# PCB.net
KiCad netlist of a schematic drawn in Altium Designer
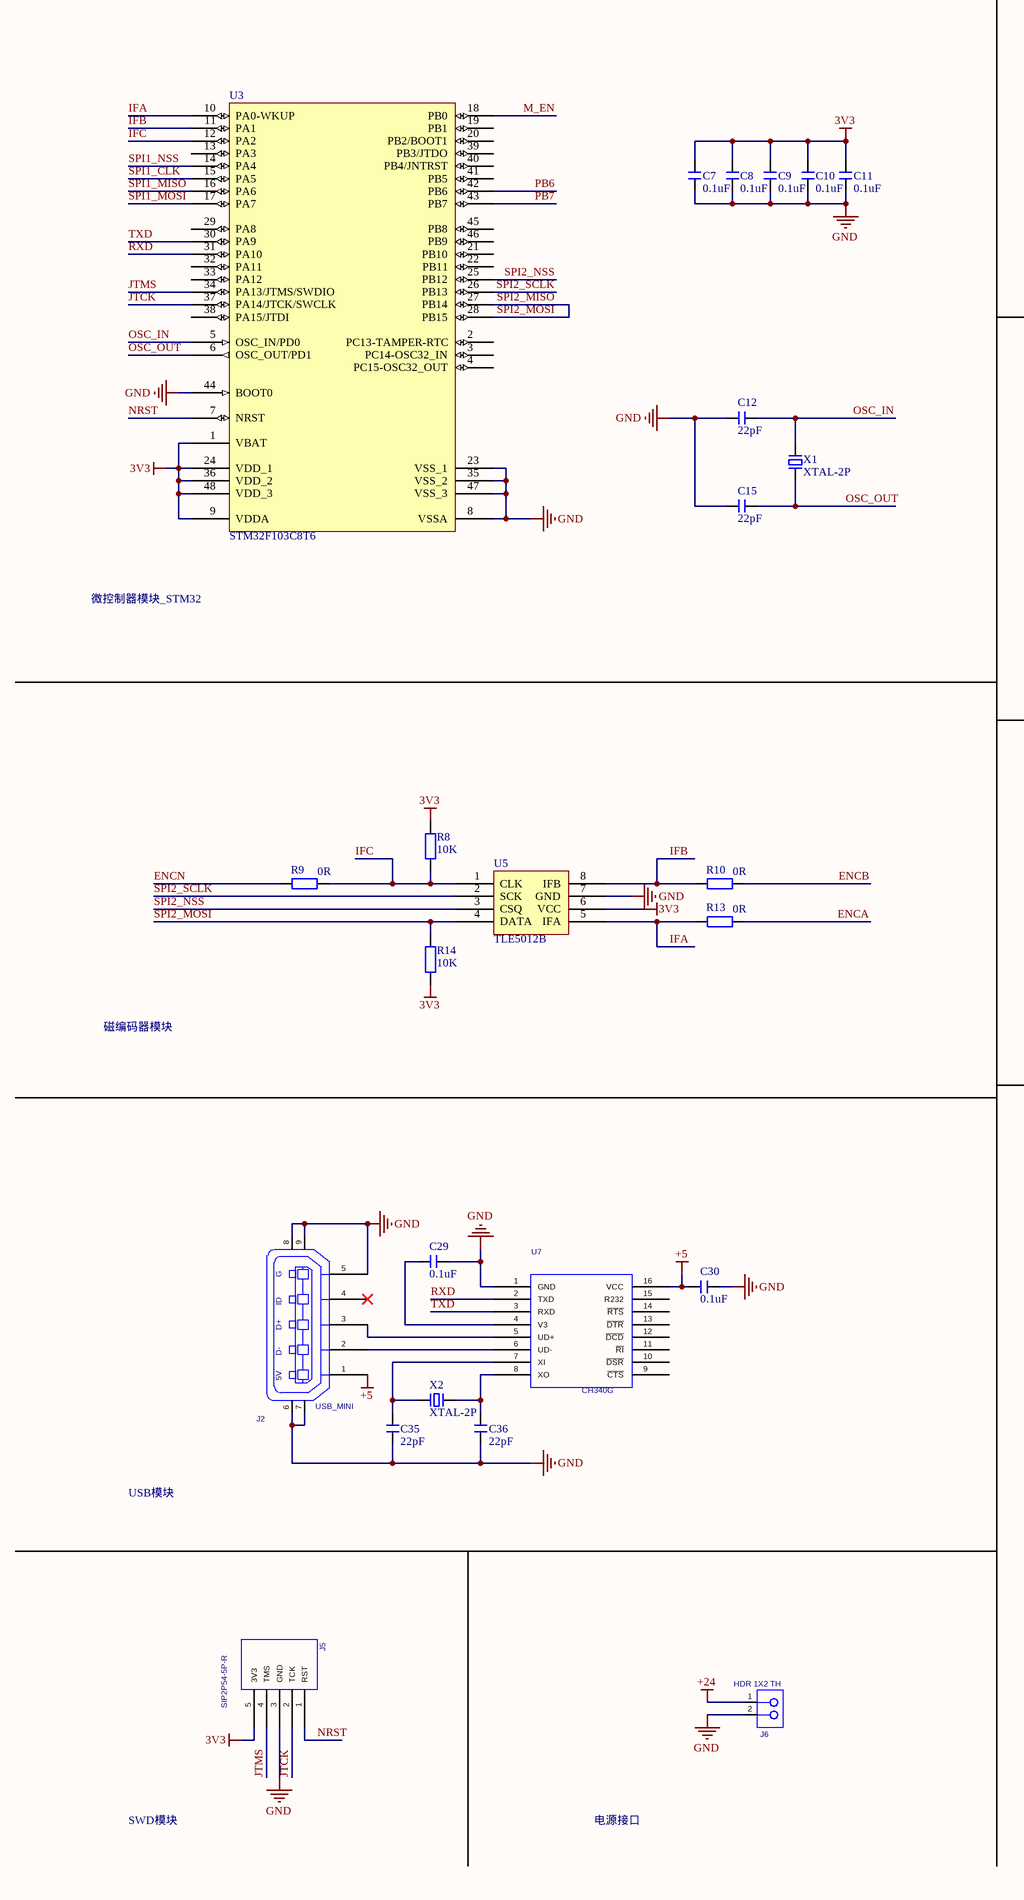
[diagram p0: PCB.SchDoc, left]
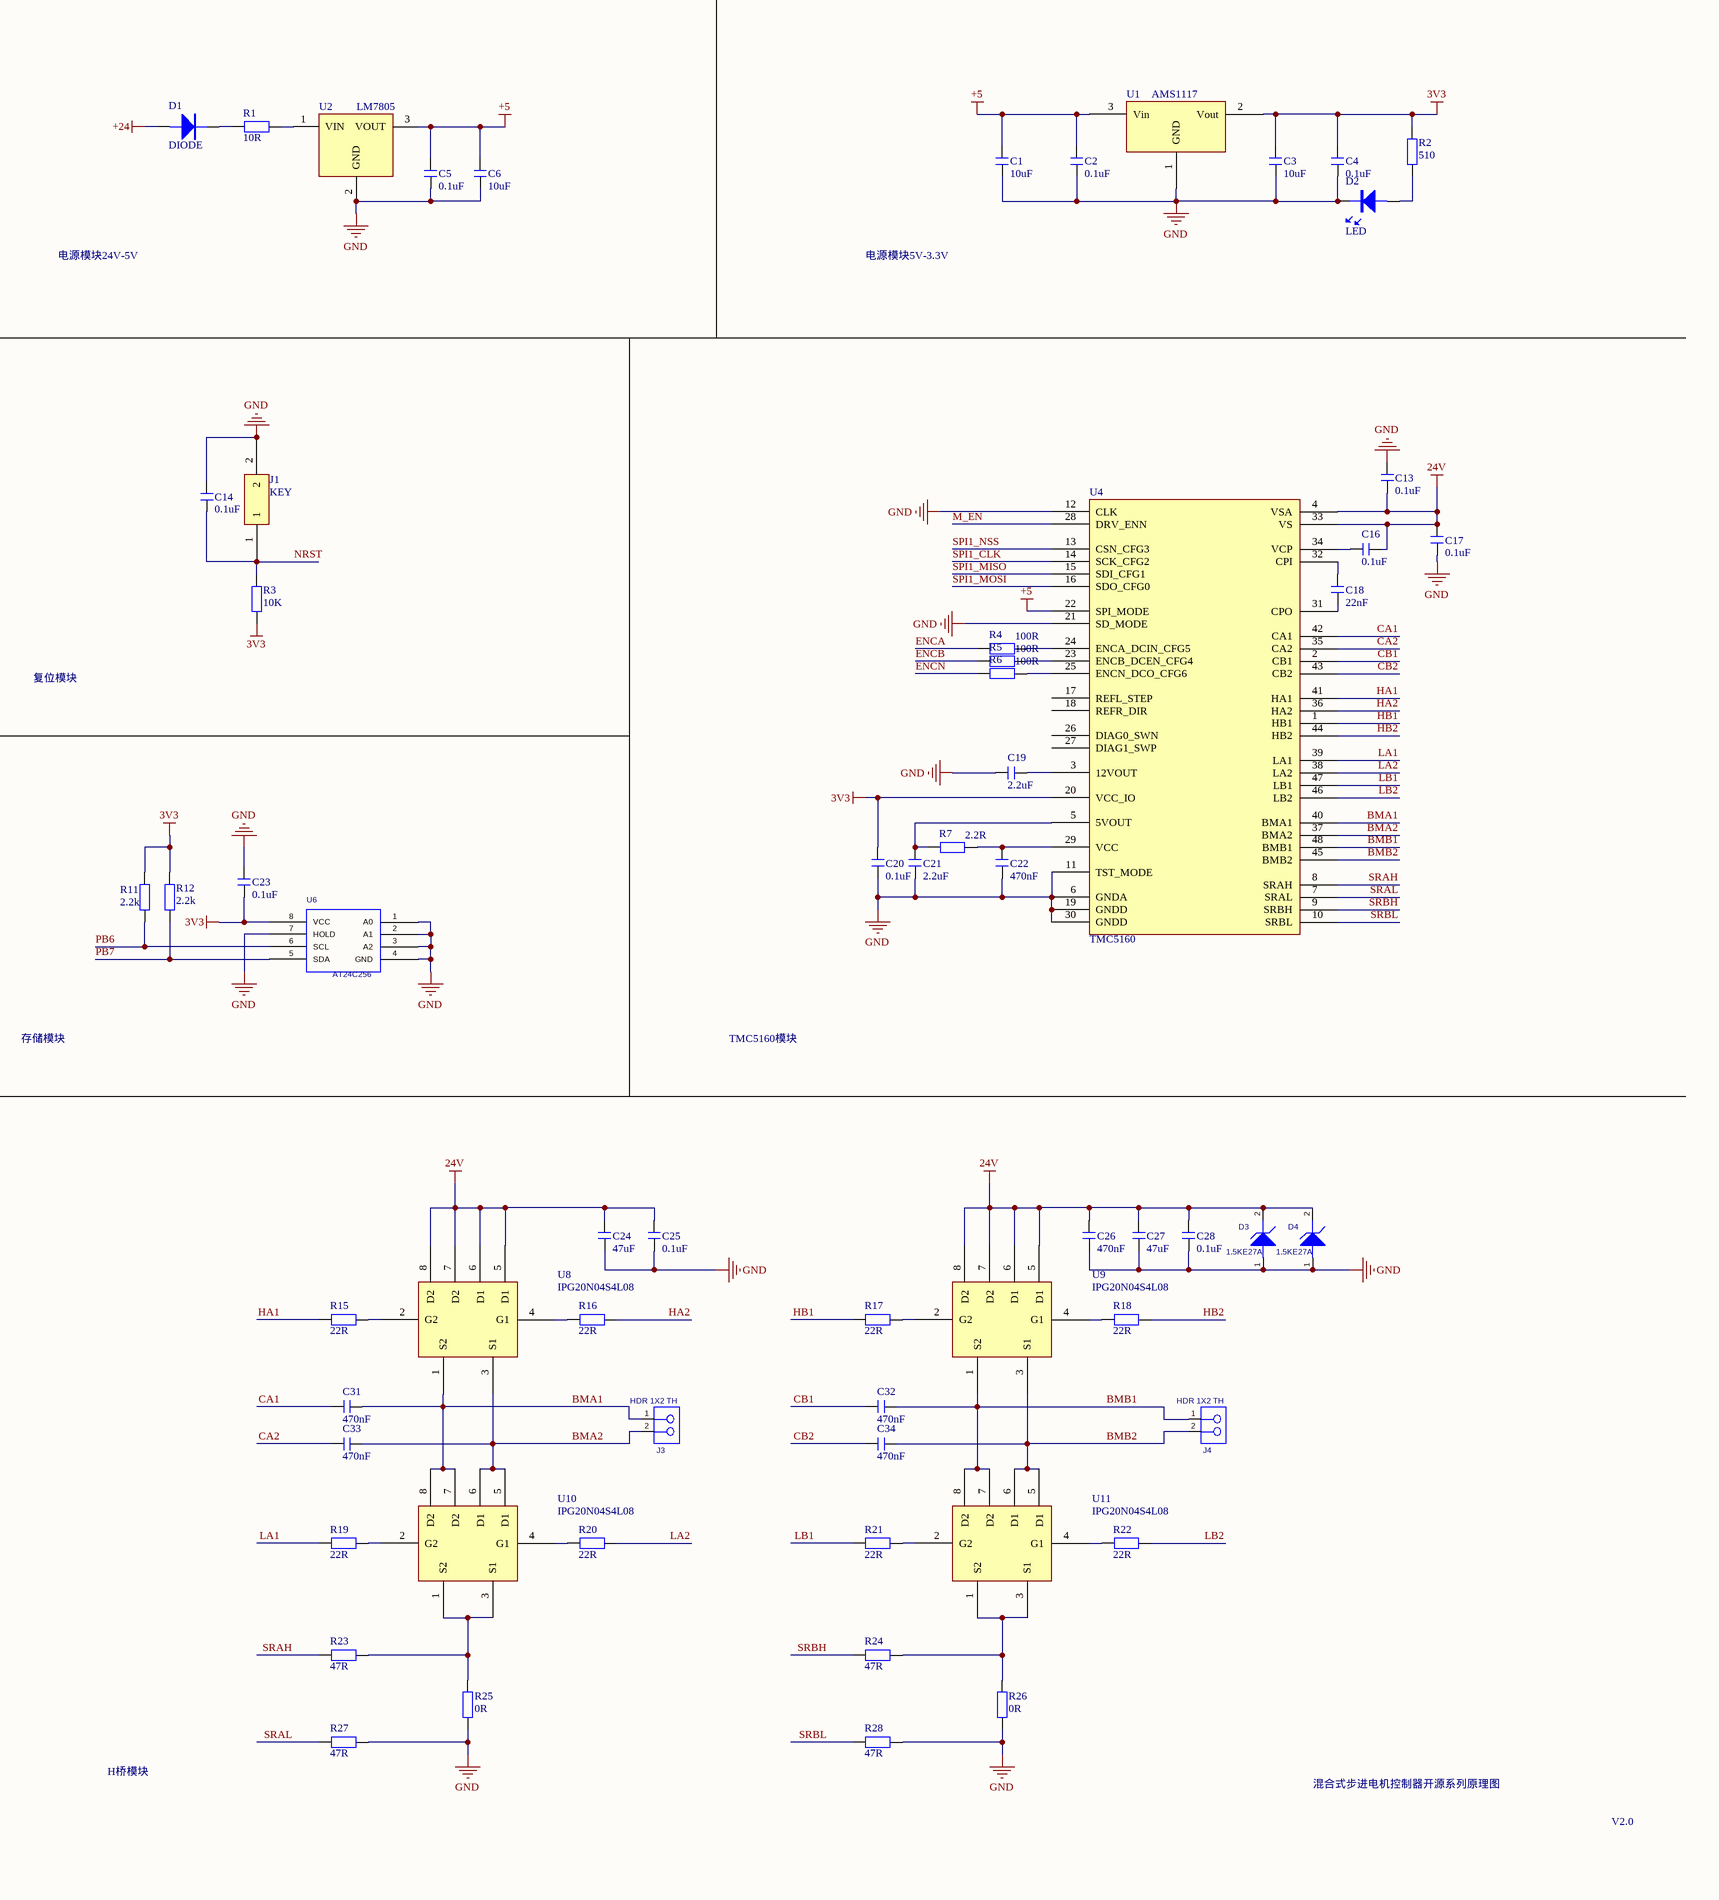
[diagram p1: PCB.SchDoc, right]

(export (version "E")
  (design (tool "Eeschema 10.0.6"))
  (components
    (comp (ref "C1")
      (value "10uF")
      (footprint "C 0805_L")
      (description "无极性贴片电容")
      (fields (field (name "版权归属") "源创客"))
      (libsource (lib "3.1   - 电阻-电容-电感") (part "C"))
    )
    (comp (ref "C2")
      (value "0.1uF")
      (footprint "C 0805_L")
      (description "无极性贴片电容")
      (fields (field (name "版权归属") "源创客"))
      (libsource (lib "3.1   - 电阻-电容-电感") (part "C"))
    )
    (comp (ref "C3")
      (value "10uF")
      (footprint "C 0805_L")
      (description "无极性贴片电容")
      (fields (field (name "版权归属") "源创客"))
      (libsource (lib "3.1   - 电阻-电容-电感") (part "C"))
    )
    (comp (ref "C4")
      (value "0.1uF")
      (footprint "C 0805_L")
      (description "无极性贴片电容")
      (fields (field (name "版权归属") "源创客"))
      (libsource (lib "3.1   - 电阻-电容-电感") (part "C"))
    )
    (comp (ref "C5")
      (value "0.1uF")
      (footprint "C 0805_L")
      (description "无极性贴片电容")
      (fields (field (name "版权归属") "源创客"))
      (libsource (lib "3.1   - 电阻-电容-电感") (part "C"))
    )
    (comp (ref "C6")
      (value "10uF")
      (footprint "C 0805_L")
      (description "无极性贴片电容")
      (fields (field (name "版权归属") "源创客"))
      (libsource (lib "3.1   - 电阻-电容-电感") (part "C"))
    )
    (comp (ref "C7")
      (value "0.1uF")
      (footprint "C 0805_L")
      (description "无极性贴片电容")
      (fields (field (name "版权归属") "源创客"))
      (libsource (lib "3.1   - 电阻-电容-电感") (part "C"))
    )
    (comp (ref "C8")
      (value "0.1uF")
      (footprint "C 0805_L")
      (description "无极性贴片电容")
      (fields (field (name "版权归属") "源创客"))
      (libsource (lib "3.1   - 电阻-电容-电感") (part "C"))
    )
    (comp (ref "C9")
      (value "0.1uF")
      (footprint "C 0805_L")
      (description "无极性贴片电容")
      (fields (field (name "版权归属") "源创客"))
      (libsource (lib "3.1   - 电阻-电容-电感") (part "C"))
    )
    (comp (ref "C10")
      (value "0.1uF")
      (footprint "C 0805_L")
      (description "无极性贴片电容")
      (fields (field (name "版权归属") "源创客"))
      (libsource (lib "3.1   - 电阻-电容-电感") (part "C"))
    )
    (comp (ref "C11")
      (value "0.1uF")
      (footprint "C 0805_L")
      (description "无极性贴片电容")
      (fields (field (name "版权归属") "源创客"))
      (libsource (lib "3.1   - 电阻-电容-电感") (part "C"))
    )
    (comp (ref "C12")
      (value "22pF")
      (footprint "C 0805_L")
      (description "无极性贴片电容")
      (fields (field (name "版权归属") "源创客"))
      (libsource (lib "3.1   - 电阻-电容-电感") (part "C"))
    )
    (comp (ref "C13")
      (value "0.1uF")
      (footprint "C 0805_L")
      (description "无极性贴片电容")
      (fields (field (name "版权归属") "源创客"))
      (libsource (lib "3.1   - 电阻-电容-电感") (part "C"))
    )
    (comp (ref "C14")
      (value "0.1uF")
      (footprint "C 0805_L")
      (description "无极性贴片电容")
      (fields (field (name "版权归属") "源创客"))
      (libsource (lib "3.1   - 电阻-电容-电感") (part "C"))
    )
    (comp (ref "C15")
      (value "22pF")
      (footprint "C 0805_L")
      (description "无极性贴片电容")
      (fields (field (name "版权归属") "源创客"))
      (libsource (lib "3.1   - 电阻-电容-电感") (part "C"))
    )
    (comp (ref "C16")
      (value "0.1uF")
      (footprint "C 0805_L")
      (description "无极性贴片电容")
      (fields (field (name "版权归属") "源创客"))
      (libsource (lib "3.1   - 电阻-电容-电感") (part "C"))
    )
    (comp (ref "C17")
      (value "0.1uF")
      (footprint "C 0805_L")
      (description "无极性贴片电容")
      (fields (field (name "版权归属") "源创客"))
      (libsource (lib "3.1   - 电阻-电容-电感") (part "C"))
    )
    (comp (ref "C18")
      (value "22nF")
      (footprint "C 0805_L")
      (description "无极性贴片电容")
      (fields (field (name "版权归属") "源创客"))
      (libsource (lib "3.1   - 电阻-电容-电感") (part "C"))
    )
    (comp (ref "C19")
      (value "2.2uF")
      (footprint "C 0805_L")
      (description "无极性贴片电容")
      (fields (field (name "版权归属") "源创客"))
      (libsource (lib "3.1   - 电阻-电容-电感") (part "C"))
    )
    (comp (ref "C20")
      (value "0.1uF")
      (footprint "C 0805_L")
      (description "无极性贴片电容")
      (fields (field (name "版权归属") "源创客"))
      (libsource (lib "3.1   - 电阻-电容-电感") (part "C"))
    )
    (comp (ref "C21")
      (value "2.2uF")
      (footprint "C 0805_L")
      (description "无极性贴片电容")
      (fields (field (name "版权归属") "源创客"))
      (libsource (lib "3.1   - 电阻-电容-电感") (part "C"))
    )
    (comp (ref "C22")
      (value "470nF")
      (footprint "C 0805_L")
      (description "无极性贴片电容")
      (fields (field (name "版权归属") "源创客"))
      (libsource (lib "3.1   - 电阻-电容-电感") (part "C"))
    )
    (comp (ref "C23")
      (value "0.1uF")
      (footprint "C 0805_L")
      (description "无极性贴片电容")
      (fields (field (name "版权归属") "源创客"))
      (libsource (lib "3.1   - 电阻-电容-电感") (part "C"))
    )
    (comp (ref "C24")
      (value "47uF")
      (footprint "C 0805_L")
      (description "无极性贴片电容")
      (fields (field (name "版权归属") "源创客"))
      (libsource (lib "3.1   - 电阻-电容-电感") (part "C"))
    )
    (comp (ref "C25")
      (value "0.1uF")
      (footprint "C 0805_L")
      (description "无极性贴片电容")
      (fields (field (name "版权归属") "源创客"))
      (libsource (lib "3.1   - 电阻-电容-电感") (part "C"))
    )
    (comp (ref "C26")
      (value "470nF")
      (footprint "C 0805_L")
      (description "无极性贴片电容")
      (fields (field (name "版权归属") "源创客"))
      (libsource (lib "3.1   - 电阻-电容-电感") (part "C"))
    )
    (comp (ref "C27")
      (value "47uF")
      (footprint "C 0805_L")
      (description "无极性贴片电容")
      (fields (field (name "版权归属") "源创客"))
      (libsource (lib "3.1   - 电阻-电容-电感") (part "C"))
    )
    (comp (ref "C28")
      (value "0.1uF")
      (footprint "C 0805_L")
      (description "无极性贴片电容")
      (fields (field (name "版权归属") "源创客"))
      (libsource (lib "3.1   - 电阻-电容-电感") (part "C"))
    )
    (comp (ref "C29")
      (value "0.1uF")
      (footprint "C 0805_L")
      (description "无极性贴片电容")
      (fields (field (name "版权归属") "源创客"))
      (libsource (lib "3.1   - 电阻-电容-电感") (part "C"))
    )
    (comp (ref "C30")
      (value "0.1uF")
      (footprint "C 0805_L")
      (description "无极性贴片电容")
      (fields (field (name "版权归属") "源创客"))
      (libsource (lib "3.1   - 电阻-电容-电感") (part "C"))
    )
    (comp (ref "C31")
      (value "470nF")
      (footprint "C 0805_L")
      (description "无极性贴片电容")
      (fields (field (name "版权归属") "源创客"))
      (libsource (lib "3.1   - 电阻-电容-电感") (part "C"))
    )
    (comp (ref "C32")
      (value "470nF")
      (footprint "C 0805_L")
      (description "无极性贴片电容")
      (fields (field (name "版权归属") "源创客"))
      (libsource (lib "3.1   - 电阻-电容-电感") (part "C"))
    )
    (comp (ref "C33")
      (value "470nF")
      (footprint "C 0805_L")
      (description "无极性贴片电容")
      (fields (field (name "版权归属") "源创客"))
      (libsource (lib "3.1   - 电阻-电容-电感") (part "C"))
    )
    (comp (ref "C34")
      (value "470nF")
      (footprint "C 0805_L")
      (description "无极性贴片电容")
      (fields (field (name "版权归属") "源创客"))
      (libsource (lib "3.1   - 电阻-电容-电感") (part "C"))
    )
    (comp (ref "C35")
      (value "22pF")
      (footprint "C 0805_L")
      (description "无极性贴片电容")
      (fields (field (name "版权归属") "源创客"))
      (libsource (lib "3.1   - 电阻-电容-电感") (part "C"))
    )
    (comp (ref "C36")
      (value "22pF")
      (footprint "C 0805_L")
      (description "无极性贴片电容")
      (fields (field (name "版权归属") "源创客"))
      (libsource (lib "3.1   - 电阻-电容-电感") (part "C"))
    )
    (comp (ref "D1")
      (value "DIODE")
      (footprint "SOD-123")
      (description "普通二极管")
      (libsource (lib "二极管") (part "DIODE"))
    )
    (comp (ref "D2") (value "LED") (footprint "LED-0805B") (libsource (lib "LED") (part "LED")))
    (comp (ref "D3")
      (value "1.5KE27A")
      (footprint "D1206")
      (description "DIODE ZNR -- 0.2W 5.1V AEC-Q101 SOD523")
      (fields (field (name "Comment") "ZDIODE_0"))
      (libsource (lib "野火_F103霸道_原理图封装_V2_0") (part "ZDIODE_0_2"))
    )
    (comp (ref "D4")
      (value "1.5KE27A")
      (footprint "D1206")
      (description "DIODE ZNR -- 0.2W 5.1V AEC-Q101 SOD523")
      (fields (field (name "Comment") "ZDIODE_0"))
      (libsource (lib "野火_F103霸道_原理图封装_V2_0") (part "ZDIODE_0_2"))
    )
    (comp (ref "J1") (value "KEY") (footprint "KEY3*4*2") (libsource (lib "F103_TMC5160_PCB") (part "KEY")))
    (comp (ref "J2")
      (value "USB_MINI")
      (footprint "MINI_USB_5S")
      (description "CON 5 USB MICRO_AB RA SKT SMT 0.65MM SP 110H AU")
      (fields (field (name "Comment") "USB_MINI_AB_RECEPTACLE_1"))
      (libsource (lib "野火_F103霸道_原理图封装_V2_0") (part "USB_MINI_AB_RECEPTACLE_1"))
    )
    (comp (ref "J3")
      (value "HDR 1X2 TH")
      (footprint "CON_2PIN")
      (description "HDR 1X2 TH 100MIL SP 339H AU 98L")
      (fields (field (name "Comment") "CONN_HDR_2X1"))
      (libsource (lib "野火_F103霸道_原理图封装_V2_0") (part "CONN_HDR_2X1"))
    )
    (comp (ref "J4")
      (value "HDR 1X2 TH")
      (footprint "CON_2PIN")
      (description "HDR 1X2 TH 100MIL SP 339H AU 98L")
      (fields (field (name "Comment") "CONN_HDR_2X1"))
      (libsource (lib "野火_F103霸道_原理图封装_V2_0") (part "CONN_HDR_2X1"))
    )
    (comp (ref "J5")
      (value "SIP2P54-5P-R")
      (footprint "XH2P54-5P_90")
      (fields (field (name "Comment") "SIP5_2_1"))
      (libsource (lib "野火_F103霸道_原理图封装_V2_0") (part "SIP5_2_1"))
    )
    (comp (ref "J6")
      (value "HDR 1X2 TH")
      (footprint "CON_2PIN")
      (description "HDR 1X2 TH 100MIL SP 339H AU 98L")
      (fields (field (name "Comment") "CONN_HDR_2X1"))
      (libsource (lib "野火_F103霸道_原理图封装_V2_0") (part "CONN_HDR_2X1"))
    )
    (comp (ref "R1")
      (value "10R")
      (footprint "R 0805_L")
      (description "贴片电阻")
      (fields (field (name "版权归属") "源创客"))
      (libsource (lib "3.1   - 电阻-电容-电感") (part "R"))
    )
    (comp (ref "R2")
      (value "510")
      (footprint "R 0805_L")
      (description "贴片电阻")
      (fields (field (name "版权归属") "源创客"))
      (libsource (lib "3.1   - 电阻-电容-电感") (part "R"))
    )
    (comp (ref "R3")
      (value "10K")
      (footprint "R 0805_L")
      (description "贴片电阻")
      (fields (field (name "版权归属") "源创客"))
      (libsource (lib "3.1   - 电阻-电容-电感") (part "R"))
    )
    (comp (ref "R4")
      (value "100R")
      (footprint "R 0805_L")
      (description "贴片电阻")
      (fields (field (name "版权归属") "源创客"))
      (libsource (lib "3.1   - 电阻-电容-电感") (part "R"))
    )
    (comp (ref "R5")
      (value "100R")
      (footprint "R 0805_L")
      (description "贴片电阻")
      (fields (field (name "版权归属") "源创客"))
      (libsource (lib "3.1   - 电阻-电容-电感") (part "R"))
    )
    (comp (ref "R6")
      (value "100R")
      (footprint "R 0805_L")
      (description "贴片电阻")
      (fields (field (name "版权归属") "源创客"))
      (libsource (lib "3.1   - 电阻-电容-电感") (part "R"))
    )
    (comp (ref "R7")
      (value "2.2R")
      (footprint "R 0805_L")
      (description "贴片电阻")
      (fields (field (name "版权归属") "源创客"))
      (libsource (lib "3.1   - 电阻-电容-电感") (part "R"))
    )
    (comp (ref "R8")
      (value "10K")
      (footprint "R 0805_L")
      (description "贴片电阻")
      (fields (field (name "版权归属") "源创客"))
      (libsource (lib "3.1   - 电阻-电容-电感") (part "R"))
    )
    (comp (ref "R9")
      (value "0R")
      (footprint "R 0805_L")
      (description "贴片电阻")
      (fields (field (name "版权归属") "源创客"))
      (libsource (lib "3.1   - 电阻-电容-电感") (part "R"))
    )
    (comp (ref "R10")
      (value "0R")
      (footprint "R 0805_L")
      (description "贴片电阻")
      (fields (field (name "版权归属") "源创客"))
      (libsource (lib "3.1   - 电阻-电容-电感") (part "R"))
    )
    (comp (ref "R11")
      (value "2.2k")
      (footprint "R 0805_L")
      (description "贴片电阻")
      (fields (field (name "版权归属") "源创客"))
      (libsource (lib "3.1   - 电阻-电容-电感") (part "R"))
    )
    (comp (ref "R12")
      (value "2.2k")
      (footprint "R 0805_L")
      (description "贴片电阻")
      (fields (field (name "版权归属") "源创客"))
      (libsource (lib "3.1   - 电阻-电容-电感") (part "R"))
    )
    (comp (ref "R13")
      (value "0R")
      (footprint "R 0805_L")
      (description "贴片电阻")
      (fields (field (name "版权归属") "源创客"))
      (libsource (lib "3.1   - 电阻-电容-电感") (part "R"))
    )
    (comp (ref "R14")
      (value "10K")
      (footprint "R 0805_L")
      (description "贴片电阻")
      (fields (field (name "版权归属") "源创客"))
      (libsource (lib "3.1   - 电阻-电容-电感") (part "R"))
    )
    (comp (ref "R15")
      (value "22R")
      (footprint "R 0805_L")
      (description "贴片电阻")
      (fields (field (name "版权归属") "源创客"))
      (libsource (lib "3.1   - 电阻-电容-电感") (part "R"))
    )
    (comp (ref "R16")
      (value "22R")
      (footprint "R 0805_L")
      (description "贴片电阻")
      (fields (field (name "版权归属") "源创客"))
      (libsource (lib "3.1   - 电阻-电容-电感") (part "R"))
    )
    (comp (ref "R17")
      (value "22R")
      (footprint "R 0805_L")
      (description "贴片电阻")
      (fields (field (name "版权归属") "源创客"))
      (libsource (lib "3.1   - 电阻-电容-电感") (part "R"))
    )
    (comp (ref "R18")
      (value "22R")
      (footprint "R 0805_L")
      (description "贴片电阻")
      (fields (field (name "版权归属") "源创客"))
      (libsource (lib "3.1   - 电阻-电容-电感") (part "R"))
    )
    (comp (ref "R19")
      (value "22R")
      (footprint "R 0805_L")
      (description "贴片电阻")
      (fields (field (name "版权归属") "源创客"))
      (libsource (lib "3.1   - 电阻-电容-电感") (part "R"))
    )
    (comp (ref "R20")
      (value "22R")
      (footprint "R 0805_L")
      (description "贴片电阻")
      (fields (field (name "版权归属") "源创客"))
      (libsource (lib "3.1   - 电阻-电容-电感") (part "R"))
    )
    (comp (ref "R21")
      (value "22R")
      (footprint "R 0805_L")
      (description "贴片电阻")
      (fields (field (name "版权归属") "源创客"))
      (libsource (lib "3.1   - 电阻-电容-电感") (part "R"))
    )
    (comp (ref "R22")
      (value "22R")
      (footprint "R 0805_L")
      (description "贴片电阻")
      (fields (field (name "版权归属") "源创客"))
      (libsource (lib "3.1   - 电阻-电容-电感") (part "R"))
    )
    (comp (ref "R23")
      (value "47R")
      (footprint "R 0805_L")
      (description "贴片电阻")
      (fields (field (name "版权归属") "源创客"))
      (libsource (lib "3.1   - 电阻-电容-电感") (part "R"))
    )
    (comp (ref "R24")
      (value "47R")
      (footprint "R 0805_L")
      (description "贴片电阻")
      (fields (field (name "版权归属") "源创客"))
      (libsource (lib "3.1   - 电阻-电容-电感") (part "R"))
    )
    (comp (ref "R25")
      (value "0R")
      (footprint "R 0805_L")
      (description "贴片电阻")
      (fields (field (name "版权归属") "源创客"))
      (libsource (lib "3.1   - 电阻-电容-电感") (part "R"))
    )
    (comp (ref "R26")
      (value "0R")
      (footprint "R 0805_L")
      (description "贴片电阻")
      (fields (field (name "版权归属") "源创客"))
      (libsource (lib "3.1   - 电阻-电容-电感") (part "R"))
    )
    (comp (ref "R27")
      (value "47R")
      (footprint "R 0805_L")
      (description "贴片电阻")
      (fields (field (name "版权归属") "源创客"))
      (libsource (lib "3.1   - 电阻-电容-电感") (part "R"))
    )
    (comp (ref "R28")
      (value "47R")
      (footprint "R 0805_L")
      (description "贴片电阻")
      (fields (field (name "版权归属") "源创客"))
      (libsource (lib "3.1   - 电阻-电容-电感") (part "R"))
    )
    (comp (ref "U1")
      (value "AMS1117")
      (footprint "SOT223")
      (description "三端稳压芯片")
      (libsource (lib "电源芯片") (part "AMS1117"))
    )
    (comp (ref "U2") (value "LM7805") (footprint "TO252") (libsource (lib "电源芯片") (part "LM7805")))
    (comp (ref "U3")
      (value "STM32F103C8T6")
      (footprint "LQFP48 7X7")
      (libsource (lib "STM32系列") (part "STM32F103C8T6"))
    )
    (comp (ref "U4")
      (value "TMC5160")
      (footprint "TQFP48 7x7")
      (libsource (lib "TMC429_SOP24") (part "TMC5160"))
    )
    (comp (ref "U5")
      (value "TLE5012B")
      (footprint "LC-SO-8_3.9mm")
      (libsource (lib "F103_TMC5160_PCB") (part "TLE5012B"))
    )
    (comp (ref "U6")
      (value "AT24C256")
      (footprint "SOP8")
      (fields
        (field (name "Comment") "AT24C02_0")
        (field (name "SOURCE_PATH") "F:\\STM32\\F407\\F407 PRO\\SCH\\野火_F407霸天虎_原理图_V2.0.DSN")
      )
      (libsource (lib "野火_F103霸道_原理图封装_V2_0") (part "AT24C02_0"))
    )
    (comp (ref "U7")
      (value "CH340G")
      (footprint "SOIC16")
      (fields (field (name "Comment") "MAX3232EEAE_1"))
      (libsource (lib "野火_F103霸道_原理图封装_V2_0") (part "MAX3232EEAE_1"))
    )
    (comp (ref "U8")
      (value "IPG20N04S4L08")
      (footprint "PG-TDSON-8_4")
      (libsource (lib "TMC429_SOP24") (part "IPG20N04S4L08"))
    )
    (comp (ref "U9")
      (value "IPG20N04S4L08")
      (footprint "PG-TDSON-8_4")
      (libsource (lib "TMC429_SOP24") (part "IPG20N04S4L08"))
    )
    (comp (ref "U10")
      (value "IPG20N04S4L08")
      (footprint "PG-TDSON-8_4")
      (libsource (lib "TMC429_SOP24") (part "IPG20N04S4L08"))
    )
    (comp (ref "U11")
      (value "IPG20N04S4L08")
      (footprint "PG-TDSON-8_4")
      (libsource (lib "TMC429_SOP24") (part "IPG20N04S4L08"))
    )
    (comp (ref "X1")
      (value "XTAL-2P")
      (footprint "OSC 5032-2P")
      (description "2脚无源脚晶振")
      (libsource (lib "晶振") (part "XTAL-2P"))
    )
    (comp (ref "X2")
      (value "XTAL-2P")
      (footprint "OSC 5032-2P")
      (description "2脚无源脚晶振")
      (libsource (lib "晶振") (part "XTAL-2P"))
    )
  )
  (nets
    (net (code "1") (name "+5") (class "Default")
      (node (ref "C1") (pin "2") (pinfunction "2_2") (pintype "passive"))
      (node (ref "C2") (pin "2") (pinfunction "2_2") (pintype "passive"))
      (node (ref "C30") (pin "2") (pinfunction "2_2") (pintype "passive"))
      (node (ref "C5") (pin "2") (pinfunction "2_2") (pintype "passive"))
      (node (ref "C6") (pin "2") (pinfunction "2_2") (pintype "passive"))
      (node (ref "J2") (pin "1") (pinfunction "P1_1") (pintype "passive"))
      (node (ref "U1") (pin "3") (pinfunction "Vin_3") (pintype "passive"))
      (node (ref "U2") (pin "3") (pinfunction "VOUT_3") (pintype "passive"))
      (node (ref "U4") (pin "22") (pinfunction "SPI_MODE_22") (pintype "passive"))
      (node (ref "U7") (pin "16") (pinfunction "VCC_16") (pintype "power_in"))
    )
    (net (code "2") (name "+24") (class "Default")
      (node (ref "D1") (pin "A") (pinfunction "A_A") (pintype "passive"))
      (node (ref "J6") (pin "1") (pinfunction "1_1") (pintype "passive"))
    )
    (net (code "3") (name "/BMA1") (class "Default")
      (node (ref "C31") (pin "2") (pinfunction "2_2") (pintype "passive"))
      (node (ref "J3") (pin "1") (pinfunction "1_1") (pintype "passive"))
      (node (ref "U10") (pin "7") (pinfunction "D2_7") (pintype "passive"))
      (node (ref "U10") (pin "8") (pinfunction "D2_8") (pintype "passive"))
      (node (ref "U4") (pin "40") (pinfunction "BMA1_40") (pintype "passive"))
      (node (ref "U8") (pin "1") (pinfunction "S2_1") (pintype "passive"))
    )
    (net (code "4") (name "/BMA2") (class "Default")
      (node (ref "C33") (pin "2") (pinfunction "2_2") (pintype "passive"))
      (node (ref "J3") (pin "2") (pinfunction "2_2") (pintype "passive"))
      (node (ref "U10") (pin "5") (pinfunction "D1_5") (pintype "passive"))
      (node (ref "U10") (pin "6") (pinfunction "D1_6") (pintype "passive"))
      (node (ref "U4") (pin "37") (pinfunction "BMA2_37") (pintype "passive"))
      (node (ref "U8") (pin "3") (pinfunction "S1_3") (pintype "passive"))
    )
    (net (code "5") (name "/BMB1") (class "Default")
      (node (ref "C32") (pin "2") (pinfunction "2_2") (pintype "passive"))
      (node (ref "J4") (pin "1") (pinfunction "1_1") (pintype "passive"))
      (node (ref "U11") (pin "7") (pinfunction "D2_7") (pintype "passive"))
      (node (ref "U11") (pin "8") (pinfunction "D2_8") (pintype "passive"))
      (node (ref "U4") (pin "48") (pinfunction "BMB1_48") (pintype "passive"))
      (node (ref "U9") (pin "1") (pinfunction "S2_1") (pintype "passive"))
    )
    (net (code "6") (name "/BMB2") (class "Default")
      (node (ref "C34") (pin "2") (pinfunction "2_2") (pintype "passive"))
      (node (ref "J4") (pin "2") (pinfunction "2_2") (pintype "passive"))
      (node (ref "U11") (pin "5") (pinfunction "D1_5") (pintype "passive"))
      (node (ref "U11") (pin "6") (pinfunction "D1_6") (pintype "passive"))
      (node (ref "U4") (pin "45") (pinfunction "BMB2_45") (pintype "passive"))
      (node (ref "U9") (pin "3") (pinfunction "S1_3") (pintype "passive"))
    )
    (net (code "7") (name "/CA1") (class "Default")
      (node (ref "C31") (pin "1") (pinfunction "1_1") (pintype "passive"))
      (node (ref "U4") (pin "42") (pinfunction "CA1_42") (pintype "passive"))
    )
    (net (code "8") (name "/CA2") (class "Default")
      (node (ref "C33") (pin "1") (pinfunction "1_1") (pintype "passive"))
      (node (ref "U4") (pin "35") (pinfunction "CA2_35") (pintype "passive"))
    )
    (net (code "9") (name "/CB1") (class "Default")
      (node (ref "C32") (pin "1") (pinfunction "1_1") (pintype "passive"))
      (node (ref "U4") (pin "2") (pinfunction "CB1_2") (pintype "passive"))
    )
    (net (code "10") (name "/CB2") (class "Default")
      (node (ref "C34") (pin "1") (pinfunction "1_1") (pintype "passive"))
      (node (ref "U4") (pin "43") (pinfunction "CB2_43") (pintype "passive"))
    )
    (net (code "11") (name "/ENCA") (class "Default")
      (node (ref "R13") (pin "1") (pinfunction "1_1") (pintype "passive"))
      (node (ref "R4") (pin "2") (pinfunction "2_2") (pintype "passive"))
    )
    (net (code "12") (name "/ENCB") (class "Default")
      (node (ref "R10") (pin "1") (pinfunction "1_1") (pintype "passive"))
      (node (ref "R5") (pin "2") (pinfunction "2_2") (pintype "passive"))
    )
    (net (code "13") (name "/ENCN") (class "Default")
      (node (ref "R6") (pin "2") (pinfunction "2_2") (pintype "passive"))
      (node (ref "R9") (pin "2") (pinfunction "2_2") (pintype "passive"))
    )
    (net (code "14") (name "/HA1") (class "Default")
      (node (ref "R15") (pin "2") (pinfunction "2_2") (pintype "passive"))
      (node (ref "U4") (pin "41") (pinfunction "HA1_41") (pintype "passive"))
    )
    (net (code "15") (name "/HA2") (class "Default")
      (node (ref "R16") (pin "1") (pinfunction "1_1") (pintype "passive"))
      (node (ref "U4") (pin "36") (pinfunction "HA2_36") (pintype "passive"))
    )
    (net (code "16") (name "/HB1") (class "Default")
      (node (ref "R17") (pin "2") (pinfunction "2_2") (pintype "passive"))
      (node (ref "U4") (pin "1") (pinfunction "HB1_1") (pintype "passive"))
    )
    (net (code "17") (name "/HB2") (class "Default")
      (node (ref "R18") (pin "1") (pinfunction "1_1") (pintype "passive"))
      (node (ref "U4") (pin "44") (pinfunction "HB2_44") (pintype "passive"))
    )
    (net (code "18") (name "/IFA") (class "Default")
      (node (ref "R13") (pin "2") (pinfunction "2_2") (pintype "passive"))
      (node (ref "U3") (pin "10") (pinfunction "PA0-WKUP_10") (pintype "bidirectional"))
      (node (ref "U5") (pin "5") (pinfunction "IFA_5") (pintype "passive"))
    )
    (net (code "19") (name "/IFB") (class "Default")
      (node (ref "R10") (pin "2") (pinfunction "2_2") (pintype "passive"))
      (node (ref "U3") (pin "11") (pinfunction "PA1_11") (pintype "bidirectional"))
      (node (ref "U5") (pin "8") (pinfunction "IFB_8") (pintype "passive"))
    )
    (net (code "20") (name "/IFC") (class "Default")
      (node (ref "R8") (pin "1") (pinfunction "1_1") (pintype "passive"))
      (node (ref "R9") (pin "1") (pinfunction "1_1") (pintype "passive"))
      (node (ref "U3") (pin "12") (pinfunction "PA2_12") (pintype "bidirectional"))
      (node (ref "U5") (pin "1") (pinfunction "CLK_1") (pintype "passive"))
    )
    (net (code "21") (name "/JTCK") (class "Default")
      (node (ref "J5") (pin "2") (pinfunction "TCK_2") (pintype "passive"))
      (node (ref "U3") (pin "37") (pinfunction "PA14/JTCK/SWCLK_37") (pintype "bidirectional"))
    )
    (net (code "22") (name "/JTMS") (class "Default")
      (node (ref "J5") (pin "4") (pinfunction "TMS_4") (pintype "passive"))
      (node (ref "U3") (pin "34") (pinfunction "PA13/JTMS/SWDIO_34") (pintype "bidirectional"))
    )
    (net (code "23") (name "/LA1") (class "Default")
      (node (ref "R19") (pin "2") (pinfunction "2_2") (pintype "passive"))
      (node (ref "U4") (pin "39") (pinfunction "LA1_39") (pintype "passive"))
    )
    (net (code "24") (name "/LA2") (class "Default")
      (node (ref "R20") (pin "1") (pinfunction "1_1") (pintype "passive"))
      (node (ref "U4") (pin "38") (pinfunction "LA2_38") (pintype "passive"))
    )
    (net (code "25") (name "/LB1") (class "Default")
      (node (ref "R21") (pin "2") (pinfunction "2_2") (pintype "passive"))
      (node (ref "U4") (pin "47") (pinfunction "LB1_47") (pintype "passive"))
    )
    (net (code "26") (name "/LB2") (class "Default")
      (node (ref "R22") (pin "1") (pinfunction "1_1") (pintype "passive"))
      (node (ref "U4") (pin "46") (pinfunction "LB2_46") (pintype "passive"))
    )
    (net (code "27") (name "/M_EN") (class "Default")
      (node (ref "U3") (pin "18") (pinfunction "PB0_18") (pintype "bidirectional"))
      (node (ref "U4") (pin "28") (pinfunction "DRV_ENN_28") (pintype "passive"))
    )
    (net (code "28") (name "/NRST") (class "Default")
      (node (ref "C14") (pin "1") (pinfunction "1_1") (pintype "passive"))
      (node (ref "J1") (pin "1") (pinfunction "1_1") (pintype "passive"))
      (node (ref "J5") (pin "1") (pinfunction "RST_1") (pintype "passive"))
      (node (ref "R3") (pin "2") (pinfunction "2_2") (pintype "passive"))
      (node (ref "U3") (pin "7") (pinfunction "NRST_7") (pintype "bidirectional"))
    )
    (net (code "29") (name "/OSC_IN") (class "Default")
      (node (ref "C12") (pin "1") (pinfunction "1_1") (pintype "passive"))
      (node (ref "U3") (pin "5") (pinfunction "OSC_IN/PD0_5") (pintype "input"))
      (node (ref "X1") (pin "2") (pinfunction "2_2") (pintype "passive"))
    )
    (net (code "30") (name "/OSC_OUT") (class "Default")
      (node (ref "C15") (pin "1") (pinfunction "1_1") (pintype "passive"))
      (node (ref "U3") (pin "6") (pinfunction "OSC_OUT/PD1_6") (pintype "output"))
      (node (ref "X1") (pin "1") (pinfunction "1_1") (pintype "passive"))
    )
    (net (code "31") (name "/PB6") (class "Default")
      (node (ref "R11") (pin "2") (pinfunction "2_2") (pintype "passive"))
      (node (ref "U3") (pin "42") (pinfunction "PB6_42") (pintype "bidirectional"))
      (node (ref "U6") (pin "6") (pinfunction "SCL_6") (pintype "passive"))
    )
    (net (code "32") (name "/PB7") (class "Default")
      (node (ref "R12") (pin "2") (pinfunction "2_2") (pintype "passive"))
      (node (ref "U3") (pin "43") (pinfunction "PB7_43") (pintype "bidirectional"))
      (node (ref "U6") (pin "5") (pinfunction "SDA_5") (pintype "passive"))
    )
    (net (code "33") (name "/RXD") (class "Default")
      (node (ref "U3") (pin "31") (pinfunction "PA10_31") (pintype "bidirectional"))
      (node (ref "U7") (pin "2") (pinfunction "TXD_2") (pintype "passive"))
    )
    (net (code "34") (name "/SPI1_CLK") (class "Default")
      (node (ref "U3") (pin "15") (pinfunction "PA5_15") (pintype "bidirectional"))
      (node (ref "U4") (pin "14") (pinfunction "SCK_CFG2_14") (pintype "passive"))
    )
    (net (code "35") (name "/SPI1_MISO") (class "Default")
      (node (ref "U3") (pin "16") (pinfunction "PA6_16") (pintype "bidirectional"))
      (node (ref "U4") (pin "15") (pinfunction "SDI_CFG1_15") (pintype "passive"))
    )
    (net (code "36") (name "/SPI1_MOSI") (class "Default")
      (node (ref "U3") (pin "17") (pinfunction "PA7_17") (pintype "bidirectional"))
      (node (ref "U4") (pin "16") (pinfunction "SDO_CFG0_16") (pintype "passive"))
    )
    (net (code "37") (name "/SPI1_NSS") (class "Default")
      (node (ref "U3") (pin "14") (pinfunction "PA4_14") (pintype "bidirectional"))
      (node (ref "U4") (pin "13") (pinfunction "CSN_CFG3_13") (pintype "passive"))
    )
    (net (code "38") (name "/SPI2_MISO") (class "Default")
      (node (ref "R14") (pin "2") (pinfunction "2_2") (pintype "passive"))
      (node (ref "U3") (pin "27") (pinfunction "PB14_27") (pintype "bidirectional"))
      (node (ref "U3") (pin "28") (pinfunction "PB15_28") (pintype "bidirectional"))
      (node (ref "U5") (pin "4") (pinfunction "DATA_4") (pintype "passive"))
    )
    (net (code "39") (name "/SPI2_NSS") (class "Default")
      (node (ref "U3") (pin "25") (pinfunction "PB12_25") (pintype "bidirectional"))
      (node (ref "U5") (pin "3") (pinfunction "CSQ_3") (pintype "passive"))
    )
    (net (code "40") (name "/SPI2_SCLK") (class "Default")
      (node (ref "U3") (pin "26") (pinfunction "PB13_26") (pintype "bidirectional"))
      (node (ref "U5") (pin "2") (pinfunction "SCK_2") (pintype "passive"))
    )
    (net (code "41") (name "/SRAH") (class "Default")
      (node (ref "R23") (pin "2") (pinfunction "2_2") (pintype "passive"))
      (node (ref "U4") (pin "8") (pinfunction "SRAH_8") (pintype "passive"))
    )
    (net (code "42") (name "/SRAL") (class "Default")
      (node (ref "R27") (pin "2") (pinfunction "2_2") (pintype "passive"))
      (node (ref "U4") (pin "7") (pinfunction "SRAL_7") (pintype "passive"))
    )
    (net (code "43") (name "/SRBH") (class "Default")
      (node (ref "R24") (pin "2") (pinfunction "2_2") (pintype "passive"))
      (node (ref "U4") (pin "9") (pinfunction "SRBH_9") (pintype "passive"))
    )
    (net (code "44") (name "/SRBL") (class "Default")
      (node (ref "R28") (pin "2") (pinfunction "2_2") (pintype "passive"))
      (node (ref "U4") (pin "10") (pinfunction "SRBL_10") (pintype "passive"))
    )
    (net (code "45") (name "/TXD") (class "Default")
      (node (ref "U3") (pin "30") (pinfunction "PA9_30") (pintype "bidirectional"))
      (node (ref "U7") (pin "3") (pinfunction "RXD_3") (pintype "passive"))
    )
    (net (code "46") (name "3V3") (class "Default")
      (node (ref "C10") (pin "2") (pinfunction "2_2") (pintype "passive"))
      (node (ref "C11") (pin "2") (pinfunction "2_2") (pintype "passive"))
      (node (ref "C20") (pin "1") (pinfunction "1_1") (pintype "passive"))
      (node (ref "C23") (pin "1") (pinfunction "1_1") (pintype "passive"))
      (node (ref "C3") (pin "2") (pinfunction "2_2") (pintype "passive"))
      (node (ref "C4") (pin "2") (pinfunction "2_2") (pintype "passive"))
      (node (ref "C7") (pin "2") (pinfunction "2_2") (pintype "passive"))
      (node (ref "C8") (pin "2") (pinfunction "2_2") (pintype "passive"))
      (node (ref "C9") (pin "2") (pinfunction "2_2") (pintype "passive"))
      (node (ref "J5") (pin "5") (pinfunction "3V3_5") (pintype "passive"))
      (node (ref "R11") (pin "1") (pinfunction "1_1") (pintype "passive"))
      (node (ref "R12") (pin "1") (pinfunction "1_1") (pintype "passive"))
      (node (ref "R14") (pin "1") (pinfunction "1_1") (pintype "passive"))
      (node (ref "R2") (pin "2") (pinfunction "2_2") (pintype "passive"))
      (node (ref "R3") (pin "1") (pinfunction "1_1") (pintype "passive"))
      (node (ref "R8") (pin "2") (pinfunction "2_2") (pintype "passive"))
      (node (ref "U1") (pin "2") (pinfunction "Vout_2") (pintype "passive"))
      (node (ref "U3") (pin "1") (pinfunction "VBAT_1") (pintype "power_in"))
      (node (ref "U3") (pin "24") (pinfunction "VDD_1_24") (pintype "power_in"))
      (node (ref "U3") (pin "36") (pinfunction "VDD_2_36") (pintype "power_in"))
      (node (ref "U3") (pin "48") (pinfunction "VDD_3_48") (pintype "power_in"))
      (node (ref "U3") (pin "9") (pinfunction "VDDA_9") (pintype "power_in"))
      (node (ref "U4") (pin "20") (pinfunction "VCC_IO_20") (pintype "passive"))
      (node (ref "U5") (pin "6") (pinfunction "VCC_6") (pintype "passive"))
      (node (ref "U6") (pin "8") (pinfunction "VCC_8") (pintype "passive"))
    )
    (net (code "47") (name "24V") (class "Default")
      (node (ref "C13") (pin "2") (pinfunction "2_2") (pintype "passive"))
      (node (ref "C16") (pin "2") (pinfunction "2_2") (pintype "passive"))
      (node (ref "C17") (pin "1") (pinfunction "1_1") (pintype "passive"))
      (node (ref "C24") (pin "1") (pinfunction "1_1") (pintype "passive"))
      (node (ref "C25") (pin "1") (pinfunction "1_1") (pintype "passive"))
      (node (ref "C26") (pin "1") (pinfunction "1_1") (pintype "passive"))
      (node (ref "C27") (pin "1") (pinfunction "1_1") (pintype "passive"))
      (node (ref "C28") (pin "1") (pinfunction "1_1") (pintype "passive"))
      (node (ref "D3") (pin "2") (pinfunction "CATHODE_2") (pintype "passive"))
      (node (ref "D4") (pin "2") (pinfunction "CATHODE_2") (pintype "passive"))
      (node (ref "U4") (pin "33") (pinfunction "VS_33") (pintype "passive"))
      (node (ref "U4") (pin "4") (pinfunction "VSA_4") (pintype "passive"))
      (node (ref "U8") (pin "5") (pinfunction "D1_5") (pintype "passive"))
      (node (ref "U8") (pin "6") (pinfunction "D1_6") (pintype "passive"))
      (node (ref "U8") (pin "7") (pinfunction "D2_7") (pintype "passive"))
      (node (ref "U8") (pin "8") (pinfunction "D2_8") (pintype "passive"))
      (node (ref "U9") (pin "5") (pinfunction "D1_5") (pintype "passive"))
      (node (ref "U9") (pin "6") (pinfunction "D1_6") (pintype "passive"))
      (node (ref "U9") (pin "7") (pinfunction "D2_7") (pintype "passive"))
      (node (ref "U9") (pin "8") (pinfunction "D2_8") (pintype "passive"))
    )
    (net (code "48") (name "GND") (class "Default")
      (node (ref "C1") (pin "1") (pinfunction "1_1") (pintype "passive"))
      (node (ref "C10") (pin "1") (pinfunction "1_1") (pintype "passive"))
      (node (ref "C11") (pin "1") (pinfunction "1_1") (pintype "passive"))
      (node (ref "C12") (pin "2") (pinfunction "2_2") (pintype "passive"))
      (node (ref "C13") (pin "1") (pinfunction "1_1") (pintype "passive"))
      (node (ref "C14") (pin "2") (pinfunction "2_2") (pintype "passive"))
      (node (ref "C15") (pin "2") (pinfunction "2_2") (pintype "passive"))
      (node (ref "C17") (pin "2") (pinfunction "2_2") (pintype "passive"))
      (node (ref "C19") (pin "2") (pinfunction "2_2") (pintype "passive"))
      (node (ref "C2") (pin "1") (pinfunction "1_1") (pintype "passive"))
      (node (ref "C20") (pin "2") (pinfunction "2_2") (pintype "passive"))
      (node (ref "C21") (pin "2") (pinfunction "2_2") (pintype "passive"))
      (node (ref "C22") (pin "2") (pinfunction "2_2") (pintype "passive"))
      (node (ref "C23") (pin "2") (pinfunction "2_2") (pintype "passive"))
      (node (ref "C24") (pin "2") (pinfunction "2_2") (pintype "passive"))
      (node (ref "C25") (pin "2") (pinfunction "2_2") (pintype "passive"))
      (node (ref "C26") (pin "2") (pinfunction "2_2") (pintype "passive"))
      (node (ref "C27") (pin "2") (pinfunction "2_2") (pintype "passive"))
      (node (ref "C28") (pin "2") (pinfunction "2_2") (pintype "passive"))
      (node (ref "C29") (pin "2") (pinfunction "2_2") (pintype "passive"))
      (node (ref "C3") (pin "1") (pinfunction "1_1") (pintype "passive"))
      (node (ref "C30") (pin "1") (pinfunction "1_1") (pintype "passive"))
      (node (ref "C35") (pin "2") (pinfunction "2_2") (pintype "passive"))
      (node (ref "C36") (pin "2") (pinfunction "2_2") (pintype "passive"))
      (node (ref "C4") (pin "1") (pinfunction "1_1") (pintype "passive"))
      (node (ref "C5") (pin "1") (pinfunction "1_1") (pintype "passive"))
      (node (ref "C6") (pin "1") (pinfunction "1_1") (pintype "passive"))
      (node (ref "C7") (pin "1") (pinfunction "1_1") (pintype "passive"))
      (node (ref "C8") (pin "1") (pinfunction "1_1") (pintype "passive"))
      (node (ref "C9") (pin "1") (pinfunction "1_1") (pintype "passive"))
      (node (ref "D2") (pin "K") (pinfunction "K_K") (pintype "passive"))
      (node (ref "D3") (pin "1") (pinfunction "ANODE_1") (pintype "passive"))
      (node (ref "D4") (pin "1") (pinfunction "ANODE_1") (pintype "passive"))
      (node (ref "J1") (pin "2") (pinfunction "2_2") (pintype "passive"))
      (node (ref "J2") (pin "5") (pinfunction "P5_5") (pintype "passive"))
      (node (ref "J2") (pin "6") (pinfunction "SHLD1_6") (pintype "passive"))
      (node (ref "J2") (pin "7") (pinfunction "SHLD3_7") (pintype "passive"))
      (node (ref "J2") (pin "8") (pinfunction "SHLD2_8") (pintype "passive"))
      (node (ref "J2") (pin "9") (pinfunction "SHLD4_9") (pintype "passive"))
      (node (ref "J5") (pin "3") (pinfunction "GND_3") (pintype "passive"))
      (node (ref "J6") (pin "2") (pinfunction "2_2") (pintype "passive"))
      (node (ref "R25") (pin "2") (pinfunction "2_2") (pintype "passive"))
      (node (ref "R26") (pin "2") (pinfunction "2_2") (pintype "passive"))
      (node (ref "R27") (pin "1") (pinfunction "1_1") (pintype "passive"))
      (node (ref "R28") (pin "1") (pinfunction "1_1") (pintype "passive"))
      (node (ref "U1") (pin "1") (pinfunction "GND_1") (pintype "passive"))
      (node (ref "U2") (pin "2") (pinfunction "GND_2") (pintype "passive"))
      (node (ref "U3") (pin "23") (pinfunction "VSS_1_23") (pintype "power_in"))
      (node (ref "U3") (pin "35") (pinfunction "VSS_2_35") (pintype "power_in"))
      (node (ref "U3") (pin "44") (pinfunction "BOOT0_44") (pintype "input"))
      (node (ref "U3") (pin "47") (pinfunction "VSS_3_47") (pintype "power_in"))
      (node (ref "U3") (pin "8") (pinfunction "VSSA_8") (pintype "power_in"))
      (node (ref "U4") (pin "11") (pinfunction "TST_MODE_11") (pintype "passive"))
      (node (ref "U4") (pin "12") (pinfunction "CLK_12") (pintype "passive"))
      (node (ref "U4") (pin "19") (pinfunction "GNDD_19") (pintype "passive"))
      (node (ref "U4") (pin "21") (pinfunction "SD_MODE_21") (pintype "passive"))
      (node (ref "U4") (pin "30") (pinfunction "GNDD_30") (pintype "passive"))
      (node (ref "U4") (pin "6") (pinfunction "GNDA_6") (pintype "passive"))
      (node (ref "U5") (pin "7") (pinfunction "GND_7") (pintype "passive"))
      (node (ref "U6") (pin "1") (pinfunction "A0_1") (pintype "passive"))
      (node (ref "U6") (pin "2") (pinfunction "A1_2") (pintype "passive"))
      (node (ref "U6") (pin "3") (pinfunction "A2_3") (pintype "passive"))
      (node (ref "U6") (pin "4") (pinfunction "GND_4") (pintype "passive"))
      (node (ref "U6") (pin "7") (pinfunction "HOLD_7") (pintype "passive"))
      (node (ref "U7") (pin "1") (pinfunction "GND_1") (pintype "passive"))
    )
    (net (code "49") (name "Net-(D1-PadK)") (class "Default")
      (node (ref "D1") (pin "K") (pinfunction "K_K") (pintype "passive"))
      (node (ref "R1") (pin "2") (pinfunction "2_2") (pintype "passive"))
    )
    (net (code "50") (name "Net-(D2-PadA)") (class "Default")
      (node (ref "D2") (pin "A") (pinfunction "A_A") (pintype "passive"))
      (node (ref "R2") (pin "1") (pinfunction "1_1") (pintype "passive"))
    )
    (net (code "51") (name "Net-(J2-P2)") (class "Default")
      (node (ref "J2") (pin "2") (pinfunction "P2_2") (pintype "passive"))
      (node (ref "U7") (pin "6") (pinfunction "UD-_6") (pintype "passive"))
    )
    (net (code "52") (name "Net-(J2-P3)") (class "Default")
      (node (ref "J2") (pin "3") (pinfunction "P3_3") (pintype "passive"))
      (node (ref "U7") (pin "5") (pinfunction "UD+_5") (pintype "passive"))
    )
    (net (code "53") (name "Net-(U2-VIN)") (class "Default")
      (node (ref "R1") (pin "1") (pinfunction "1_1") (pintype "passive"))
      (node (ref "U2") (pin "1") (pinfunction "VIN_1") (pintype "passive"))
    )
    (net (code "54") (name "Net-(U4-5VOUT)") (class "Default")
      (node (ref "C21") (pin "1") (pinfunction "1_1") (pintype "passive"))
      (node (ref "R7") (pin "2") (pinfunction "2_2") (pintype "passive"))
      (node (ref "U4") (pin "5") (pinfunction "5VOUT_5") (pintype "passive"))
    )
    (net (code "55") (name "Net-(U4-12VOUT)") (class "Default")
      (node (ref "C19") (pin "1") (pinfunction "1_1") (pintype "passive"))
      (node (ref "U4") (pin "3") (pinfunction "12VOUT_3") (pintype "passive"))
    )
    (net (code "56") (name "Net-(U4-CPI)") (class "Default")
      (node (ref "C18") (pin "1") (pinfunction "1_1") (pintype "passive"))
      (node (ref "U4") (pin "32") (pinfunction "CPI_32") (pintype "passive"))
    )
    (net (code "57") (name "Net-(U4-CPO)") (class "Default")
      (node (ref "C18") (pin "2") (pinfunction "2_2") (pintype "passive"))
      (node (ref "U4") (pin "31") (pinfunction "CPO_31") (pintype "passive"))
    )
    (net (code "58") (name "Net-(U4-ENCA_DCIN_CFG5)") (class "Default")
      (node (ref "R4") (pin "1") (pinfunction "1_1") (pintype "passive"))
      (node (ref "U4") (pin "24") (pinfunction "ENCA_DCIN_CFG5_24") (pintype "passive"))
    )
    (net (code "59") (name "Net-(U4-ENCB_DCEN_CFG4)") (class "Default")
      (node (ref "R5") (pin "1") (pinfunction "1_1") (pintype "passive"))
      (node (ref "U4") (pin "23") (pinfunction "ENCB_DCEN_CFG4_23") (pintype "passive"))
    )
    (net (code "60") (name "Net-(U4-ENCN_DCO_CFG6)") (class "Default")
      (node (ref "R6") (pin "1") (pinfunction "1_1") (pintype "passive"))
      (node (ref "U4") (pin "25") (pinfunction "ENCN_DCO_CFG6_25") (pintype "passive"))
    )
    (net (code "61") (name "Net-(U4-VCC)") (class "Default")
      (node (ref "C22") (pin "1") (pinfunction "1_1") (pintype "passive"))
      (node (ref "R7") (pin "1") (pinfunction "1_1") (pintype "passive"))
      (node (ref "U4") (pin "29") (pinfunction "VCC_29") (pintype "passive"))
    )
    (net (code "62") (name "Net-(U4-VCP)") (class "Default")
      (node (ref "C16") (pin "1") (pinfunction "1_1") (pintype "passive"))
      (node (ref "U4") (pin "34") (pinfunction "VCP_34") (pintype "passive"))
    )
    (net (code "63") (name "Net-(U7-V3)") (class "Default")
      (node (ref "C29") (pin "1") (pinfunction "1_1") (pintype "passive"))
      (node (ref "U7") (pin "4") (pinfunction "V3_4") (pintype "passive"))
    )
    (net (code "64") (name "Net-(U7-XI)") (class "Default")
      (node (ref "C35") (pin "1") (pinfunction "1_1") (pintype "passive"))
      (node (ref "U7") (pin "7") (pinfunction "XI_7") (pintype "passive"))
      (node (ref "X2") (pin "2") (pinfunction "2_2") (pintype "passive"))
    )
    (net (code "65") (name "Net-(U7-XO)") (class "Default")
      (node (ref "C36") (pin "1") (pinfunction "1_1") (pintype "passive"))
      (node (ref "U7") (pin "8") (pinfunction "XO_8") (pintype "passive"))
      (node (ref "X2") (pin "1") (pinfunction "1_1") (pintype "passive"))
    )
    (net (code "66") (name "Net-(U8-G1)") (class "Default")
      (node (ref "R16") (pin "2") (pinfunction "2_2") (pintype "passive"))
      (node (ref "U8") (pin "4") (pinfunction "G1_4") (pintype "passive"))
    )
    (net (code "67") (name "Net-(U8-G2)") (class "Default")
      (node (ref "R15") (pin "1") (pinfunction "1_1") (pintype "passive"))
      (node (ref "U8") (pin "2") (pinfunction "G2_2") (pintype "passive"))
    )
    (net (code "68") (name "Net-(U9-G1)") (class "Default")
      (node (ref "R18") (pin "2") (pinfunction "2_2") (pintype "passive"))
      (node (ref "U9") (pin "4") (pinfunction "G1_4") (pintype "passive"))
    )
    (net (code "69") (name "Net-(U9-G2)") (class "Default")
      (node (ref "R17") (pin "1") (pinfunction "1_1") (pintype "passive"))
      (node (ref "U9") (pin "2") (pinfunction "G2_2") (pintype "passive"))
    )
    (net (code "70") (name "Net-(U10-G1)") (class "Default")
      (node (ref "R20") (pin "2") (pinfunction "2_2") (pintype "passive"))
      (node (ref "U10") (pin "4") (pinfunction "G1_4") (pintype "passive"))
    )
    (net (code "71") (name "Net-(U10-G2)") (class "Default")
      (node (ref "R19") (pin "1") (pinfunction "1_1") (pintype "passive"))
      (node (ref "U10") (pin "2") (pinfunction "G2_2") (pintype "passive"))
    )
    (net (code "72") (name "Net-(U10-S1)") (class "Default")
      (node (ref "R23") (pin "1") (pinfunction "1_1") (pintype "passive"))
      (node (ref "R25") (pin "1") (pinfunction "1_1") (pintype "passive"))
      (node (ref "U10") (pin "1") (pinfunction "S2_1") (pintype "passive"))
      (node (ref "U10") (pin "3") (pinfunction "S1_3") (pintype "passive"))
    )
    (net (code "73") (name "Net-(U11-G1)") (class "Default")
      (node (ref "R22") (pin "2") (pinfunction "2_2") (pintype "passive"))
      (node (ref "U11") (pin "4") (pinfunction "G1_4") (pintype "passive"))
    )
    (net (code "74") (name "Net-(U11-G2)") (class "Default")
      (node (ref "R21") (pin "1") (pinfunction "1_1") (pintype "passive"))
      (node (ref "U11") (pin "2") (pinfunction "G2_2") (pintype "passive"))
    )
    (net (code "75") (name "Net-(U11-S1)") (class "Default")
      (node (ref "R24") (pin "1") (pinfunction "1_1") (pintype "passive"))
      (node (ref "R26") (pin "1") (pinfunction "1_1") (pintype "passive"))
      (node (ref "U11") (pin "1") (pinfunction "S2_1") (pintype "passive"))
      (node (ref "U11") (pin "3") (pinfunction "S1_3") (pintype "passive"))
    )
    (net (code "76") (name "unconnected-(J2-P4-Pad4)") (class "Default")
      (node (ref "J2") (pin "4") (pinfunction "P4_4") (pintype "passive+no_connect"))
    )
    (net (code "77") (name "unconnected-(U3-PA3-Pad13)") (class "Default")
      (node (ref "U3") (pin "13") (pinfunction "PA3_13") (pintype "bidirectional"))
    )
    (net (code "78") (name "unconnected-(U3-PA8-Pad29)") (class "Default")
      (node (ref "U3") (pin "29") (pinfunction "PA8_29") (pintype "bidirectional"))
    )
    (net (code "79") (name "unconnected-(U3-PA11-Pad32)") (class "Default")
      (node (ref "U3") (pin "32") (pinfunction "PA11_32") (pintype "bidirectional"))
    )
    (net (code "80") (name "unconnected-(U3-PA12-Pad33)") (class "Default")
      (node (ref "U3") (pin "33") (pinfunction "PA12_33") (pintype "bidirectional"))
    )
    (net (code "81") (name "unconnected-(U3-PA15{slash}JTDI-Pad38)") (class "Default")
      (node (ref "U3") (pin "38") (pinfunction "PA15/JTDI_38") (pintype "bidirectional"))
    )
    (net (code "82") (name "unconnected-(U3-PB1-Pad19)") (class "Default")
      (node (ref "U3") (pin "19") (pinfunction "PB1_19") (pintype "bidirectional"))
    )
    (net (code "83") (name "unconnected-(U3-PB2{slash}BOOT1-Pad20)") (class "Default")
      (node (ref "U3") (pin "20") (pinfunction "PB2/BOOT1_20") (pintype "bidirectional"))
    )
    (net (code "84") (name "unconnected-(U3-PB3{slash}JTDO-Pad39)") (class "Default")
      (node (ref "U3") (pin "39") (pinfunction "PB3/JTDO_39") (pintype "bidirectional"))
    )
    (net (code "85") (name "unconnected-(U3-PB4{slash}JNTRST-Pad40)") (class "Default")
      (node (ref "U3") (pin "40") (pinfunction "PB4/JNTRST_40") (pintype "bidirectional"))
    )
    (net (code "86") (name "unconnected-(U3-PB5-Pad41)") (class "Default")
      (node (ref "U3") (pin "41") (pinfunction "PB5_41") (pintype "bidirectional"))
    )
    (net (code "87") (name "unconnected-(U3-PB8-Pad45)") (class "Default")
      (node (ref "U3") (pin "45") (pinfunction "PB8_45") (pintype "bidirectional"))
    )
    (net (code "88") (name "unconnected-(U3-PB9-Pad46)") (class "Default")
      (node (ref "U3") (pin "46") (pinfunction "PB9_46") (pintype "bidirectional"))
    )
    (net (code "89") (name "unconnected-(U3-PB10-Pad21)") (class "Default")
      (node (ref "U3") (pin "21") (pinfunction "PB10_21") (pintype "bidirectional"))
    )
    (net (code "90") (name "unconnected-(U3-PB11-Pad22)") (class "Default")
      (node (ref "U3") (pin "22") (pinfunction "PB11_22") (pintype "bidirectional"))
    )
    (net (code "91") (name "unconnected-(U3-PC13-TAMPER-RTC-Pad2)") (class "Default")
      (node (ref "U3") (pin "2") (pinfunction "PC13-TAMPER-RTC_2") (pintype "bidirectional"))
    )
    (net (code "92") (name "unconnected-(U3-PC14-OSC32_IN-Pad3)") (class "Default")
      (node (ref "U3") (pin "3") (pinfunction "PC14-OSC32_IN_3") (pintype "bidirectional"))
    )
    (net (code "93") (name "unconnected-(U3-PC15-OSC32_OUT-Pad4)") (class "Default")
      (node (ref "U3") (pin "4") (pinfunction "PC15-OSC32_OUT_4") (pintype "bidirectional"))
    )
    (net (code "94") (name "unconnected-(U4-DIAG0_SWN-Pad26)") (class "Default")
      (node (ref "U4") (pin "26") (pinfunction "DIAG0_SWN_26") (pintype "passive"))
    )
    (net (code "95") (name "unconnected-(U4-DIAG1_SWP-Pad27)") (class "Default")
      (node (ref "U4") (pin "27") (pinfunction "DIAG1_SWP_27") (pintype "passive"))
    )
    (net (code "96") (name "unconnected-(U4-REFL_STEP-Pad17)") (class "Default")
      (node (ref "U4") (pin "17") (pinfunction "REFL_STEP_17") (pintype "passive"))
    )
    (net (code "97") (name "unconnected-(U4-REFR_DIR-Pad18)") (class "Default")
      (node (ref "U4") (pin "18") (pinfunction "REFR_DIR_18") (pintype "passive"))
    )
    (net (code "98") (name "unconnected-(U7-CTS-Pad9)") (class "Default")
      (node (ref "U7") (pin "9") (pinfunction "CTS_9") (pintype "passive"))
    )
    (net (code "99") (name "unconnected-(U7-DCD-Pad12)") (class "Default")
      (node (ref "U7") (pin "12") (pinfunction "DCD_12") (pintype "passive"))
    )
    (net (code "100") (name "unconnected-(U7-DSR-Pad10)") (class "Default")
      (node (ref "U7") (pin "10") (pinfunction "DSR_10") (pintype "passive"))
    )
    (net (code "101") (name "unconnected-(U7-DTR-Pad13)") (class "Default")
      (node (ref "U7") (pin "13") (pinfunction "DTR_13") (pintype "passive"))
    )
    (net (code "102") (name "unconnected-(U7-R232-Pad15)") (class "Default")
      (node (ref "U7") (pin "15") (pinfunction "R232_15") (pintype "passive"))
    )
    (net (code "103") (name "unconnected-(U7-RI-Pad11)") (class "Default")
      (node (ref "U7") (pin "11") (pinfunction "RI_11") (pintype "passive"))
    )
    (net (code "104") (name "unconnected-(U7-RTS-Pad14)") (class "Default")
      (node (ref "U7") (pin "14") (pinfunction "RTS_14") (pintype "passive"))
    )
  )
)
